# compass.net
KiCad netlist of a schematic drawn in EAGLE
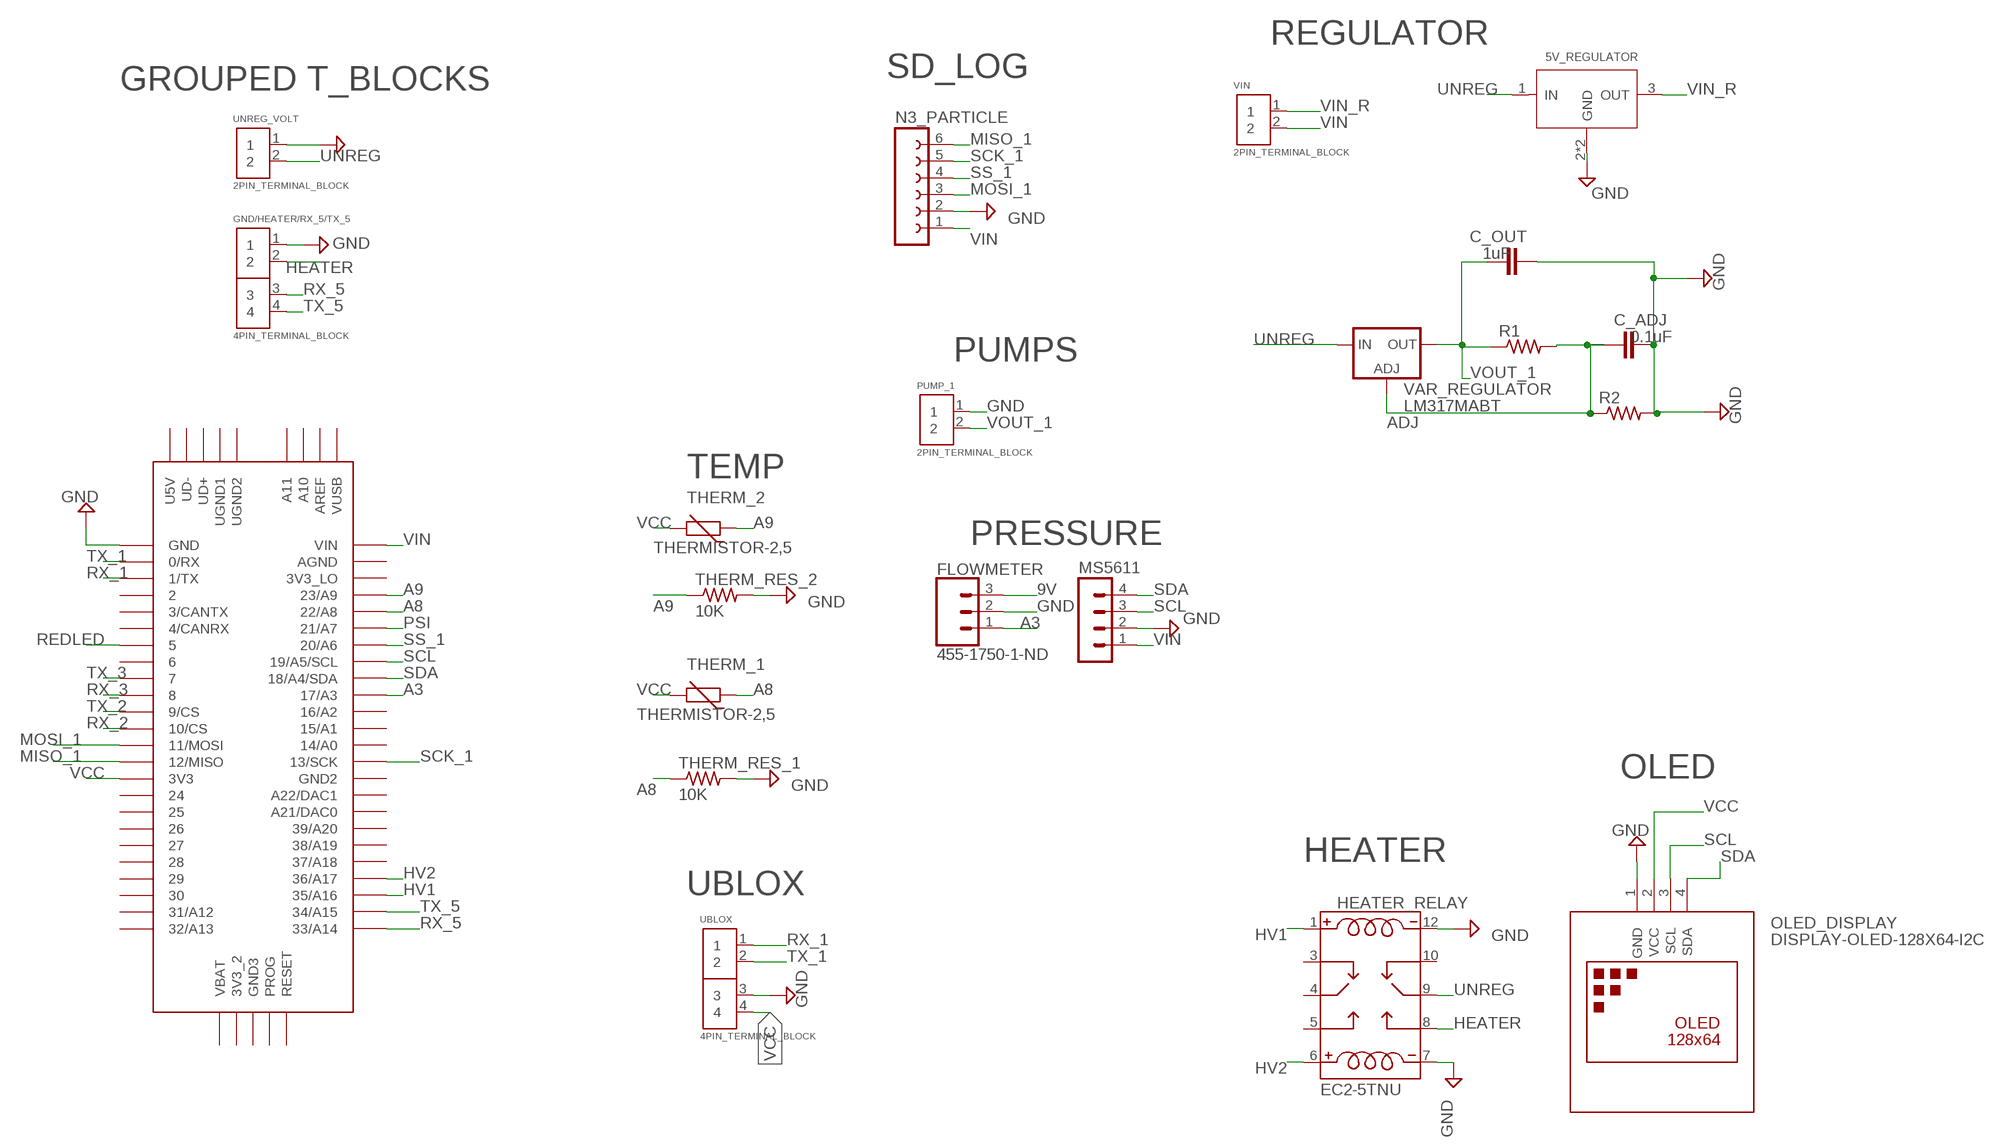
[diagram p0: schematic, sheet 1]

(export (version "E")
  (design (tool "Eeschema 10.0.6"))
  (components
    (comp (ref "5V_REGULATOR")
      (value "PMIC-L7805CV-DG(TO-220)")
      (footprint "eagle-import:TO-220")
      (fields
        (field (name "DIGI-KEY_PART_NUMBER") "497-12404-ND")
        (field (name "MF") "STMicroelectronics")
        (field (name "MP") "L7805CV-DG")
      )
      (libsource (lib "eagle-import") (part "PMIC-L7805CV-DG(TO-220)"))
    )
    (comp (ref "C_ADJ")
      (value "0.1uF")
      (footprint "eagle-import:C2.5-3")
      (libsource (lib "eagle-import") (part "C2,5-3"))
    )
    (comp (ref "C_OUT")
      (value "1uF")
      (footprint "eagle-import:C2.5-3")
      (libsource (lib "eagle-import") (part "C2,5-3"))
    )
    (comp (ref "FLOWMETER")
      (value "455-1750-1-ND")
      (footprint "eagle-import:1X03")
      (libsource (lib "eagle-import") (part "CONN_03"))
    )
    (comp (ref "GND/HEATER/RX_5/TX_5")
      (value "4PIN_TERMINAL_BLOCK")
      (footprint "eagle-import:4PIN_TERMINAL_BLOCK")
      (libsource (lib "eagle-import") (part "4PIN_TERMINAL_BLOCK"))
    )
    (comp (ref "HEATER_RELAY")
      (value "EC2-5TNU")
      (footprint "eagle-import:RELAY_EC2-5TNU")
      (fields (field (name "MF") "KEMET"))
      (libsource (lib "eagle-import") (part "EC2-5TNU"))
    )
    (comp (ref "MS5611")
      (value "MA04-1")
      (footprint "eagle-import:MA04-1")
      (libsource (lib "eagle-import") (part "MA04-1"))
    )
    (comp (ref "N3_PARTICLE")
      (value "FE06-1")
      (footprint "eagle-import:FE06")
      (libsource (lib "eagle-import") (part "FE06-1"))
    )
    (comp (ref "OLED_DISPLAY")
      (value "DISPLAY-OLED-128X64-I2C")
      (footprint "eagle-import:DISPLAY-OLED-128X64-I2C")
      (libsource (lib "eagle-import") (part "DISPLAY-OLED-128X64-I2C"))
    )
    (comp (ref "PUMP_1")
      (value "2PIN_TERMINAL_BLOCK")
      (footprint "eagle-import:2PIN_TERMINAL_BLOCK")
      (fields
        (field (name "COMMENT") "282834-2")
        (field (name "DIGI-KEY_PART_NUMBER") "A98333-ND")
        (field (name "MF") "TE Connectivity")
      )
      (libsource (lib "eagle-import") (part "2PIN_TERMINAL_BLOCK"))
    )
    (comp (ref "R1")
      (value "R-US_0204/7")
      (footprint "eagle-import:0204_7")
      (libsource (lib "eagle-import") (part "R-US_0204/7"))
    )
    (comp (ref "R2")
      (value "R-US_0204/7")
      (footprint "eagle-import:0204_7")
      (libsource (lib "eagle-import") (part "R-US_0204/7"))
    )
    (comp (ref "THERM_1")
      (value "THERMISTOR-2,5")
      (footprint "eagle-import:RS-2,5")
      (libsource (lib "eagle-import") (part "THERMISTOR-2,5"))
    )
    (comp (ref "THERM_2")
      (value "THERMISTOR-2,5")
      (footprint "eagle-import:RS-2,5")
      (libsource (lib "eagle-import") (part "THERMISTOR-2,5"))
    )
    (comp (ref "THERM_RES_1")
      (value "10K")
      (footprint "eagle-import:0204_7")
      (libsource (lib "eagle-import") (part "R-US_0204/7"))
    )
    (comp (ref "THERM_RES_2")
      (value "10K")
      (footprint "eagle-import:0204_7")
      (libsource (lib "eagle-import") (part "R-US_0204/7"))
    )
    (comp (ref "U$1")
      (value "TEENSY_3.5/3.6")
      (footprint "eagle-import:TEENSY_3.5_3.6")
      (libsource (lib "eagle-import") (part "TEENSY_3.5/3.6"))
    )
    (comp (ref "UBLOX")
      (value "4PIN_TERMINAL_BLOCK")
      (footprint "eagle-import:4PIN_TERMINAL_BLOCK")
      (libsource (lib "eagle-import") (part "4PIN_TERMINAL_BLOCK"))
    )
    (comp (ref "UNREG_VOLT")
      (value "2PIN_TERMINAL_BLOCK")
      (footprint "eagle-import:2PIN_TERMINAL_BLOCK")
      (fields
        (field (name "COMMENT") "282834-2")
        (field (name "DIGI-KEY_PART_NUMBER") "A98333-ND")
        (field (name "MF") "TE Connectivity")
      )
      (libsource (lib "eagle-import") (part "2PIN_TERMINAL_BLOCK"))
    )
    (comp (ref "VAR_REGULATOR")
      (value "LM317MABT")
      (footprint "eagle-import:TO220L1")
      (libsource (lib "eagle-import") (part "LM317?MABT"))
    )
    (comp (ref "VIN")
      (value "2PIN_TERMINAL_BLOCK")
      (footprint "eagle-import:2PIN_TERMINAL_BLOCK")
      (fields
        (field (name "COMMENT") "282834-2")
        (field (name "DIGI-KEY_PART_NUMBER") "A98333-ND")
        (field (name "MF") "TE Connectivity")
      )
      (libsource (lib "eagle-import") (part "2PIN_TERMINAL_BLOCK"))
    )
  )
  (nets
    (net (code "1") (name "/9V") (class "Default")
      (node (ref "FLOWMETER") (pin "3") (pinfunction "3_3") (pintype "passive"))
    )
    (net (code "2") (name "/A3") (class "Default")
      (node (ref "FLOWMETER") (pin "1") (pinfunction "1_1") (pintype "passive"))
      (node (ref "U$1") (pin "17/A3") (pinfunction "17/A3_17/A3") (pintype "bidirectional"))
    )
    (net (code "3") (name "/A8") (class "Default")
      (node (ref "THERM_1") (pin "1") (pinfunction "1_1") (pintype "passive"))
      (node (ref "THERM_RES_1") (pin "1") (pinfunction "1_1") (pintype "passive"))
      (node (ref "U$1") (pin "22/A8") (pinfunction "22/A8_22/A8") (pintype "bidirectional"))
    )
    (net (code "4") (name "/A9") (class "Default")
      (node (ref "THERM_2") (pin "1") (pinfunction "1_1") (pintype "passive"))
      (node (ref "THERM_RES_2") (pin "1") (pinfunction "1_1") (pintype "passive"))
      (node (ref "U$1") (pin "23/A9") (pinfunction "23/A9_23/A9") (pintype "bidirectional"))
    )
    (net (code "5") (name "/ADJ") (class "Default")
      (node (ref "C_ADJ") (pin "2") (pinfunction "2_2") (pintype "passive"))
      (node (ref "R1") (pin "2") (pinfunction "2_2") (pintype "passive"))
      (node (ref "R2") (pin "1") (pinfunction "1_1") (pintype "passive"))
      (node (ref "VAR_REGULATOR") (pin "1") (pinfunction "ADJ_1") (pintype "input"))
    )
    (net (code "6") (name "/HEATER") (class "Default")
      (node (ref "GND/HEATER/RX_5/TX_5") (pin "2") (pinfunction "2_2") (pintype "passive"))
      (node (ref "HEATER_RELAY") (pin "8") (pinfunction "NO_8") (pintype "passive"))
    )
    (net (code "7") (name "/HV1") (class "Default")
      (node (ref "HEATER_RELAY") (pin "1") (pinfunction "C1_1") (pintype "passive"))
      (node (ref "U$1") (pin "35/A16") (pinfunction "35/A16_35/A16") (pintype "bidirectional"))
    )
    (net (code "8") (name "/HV2") (class "Default")
      (node (ref "HEATER_RELAY") (pin "6") (pinfunction "C3_6") (pintype "passive"))
      (node (ref "U$1") (pin "36/A17") (pinfunction "36/A17_36/A17") (pintype "bidirectional"))
    )
    (net (code "9") (name "/MISO_1") (class "Default")
      (node (ref "N3_PARTICLE") (pin "6") (pinfunction "6_6") (pintype "passive"))
      (node (ref "U$1") (pin "12/MISO") (pinfunction "12/MISO_12/MISO") (pintype "bidirectional"))
    )
    (net (code "10") (name "/MOSI_1") (class "Default")
      (node (ref "N3_PARTICLE") (pin "3") (pinfunction "3_3") (pintype "passive"))
      (node (ref "U$1") (pin "11/MOSI") (pinfunction "11/MOSI_11/MOSI") (pintype "bidirectional"))
    )
    (net (code "11") (name "/PSI") (class "Default")
      (node (ref "U$1") (pin "21/A7") (pinfunction "21/A7_21/A7") (pintype "bidirectional"))
    )
    (net (code "12") (name "/REDLED") (class "Default")
      (node (ref "U$1") (pin "5") (pinfunction "5_5") (pintype "bidirectional"))
    )
    (net (code "13") (name "/RX_1") (class "Default")
      (node (ref "U$1") (pin "1/TX") (pinfunction "1/TX_1/TX") (pintype "bidirectional"))
      (node (ref "UBLOX") (pin "1") (pinfunction "1_1") (pintype "passive"))
    )
    (net (code "14") (name "/RX_2") (class "Default")
      (node (ref "U$1") (pin "10/CS") (pinfunction "10/CS_10/CS") (pintype "bidirectional"))
    )
    (net (code "15") (name "/RX_3") (class "Default")
      (node (ref "U$1") (pin "8") (pinfunction "8_8") (pintype "bidirectional"))
    )
    (net (code "16") (name "/RX_5") (class "Default")
      (node (ref "GND/HEATER/RX_5/TX_5") (pin "3") (pinfunction "3_3") (pintype "passive"))
      (node (ref "U$1") (pin "33/A14") (pinfunction "33/A14_33/A14") (pintype "bidirectional"))
    )
    (net (code "17") (name "/SCK_1") (class "Default")
      (node (ref "N3_PARTICLE") (pin "5") (pinfunction "5_5") (pintype "passive"))
      (node (ref "U$1") (pin "13/SCK") (pinfunction "13/SCK_13/SCK") (pintype "bidirectional"))
    )
    (net (code "18") (name "/SCL") (class "Default")
      (node (ref "MS5611") (pin "3") (pinfunction "3_3") (pintype "passive"))
      (node (ref "OLED_DISPLAY") (pin "3") (pinfunction "SCL_3") (pintype "bidirectional"))
      (node (ref "U$1") (pin "19/A5/SCL") (pinfunction "19/A5/SCL_19/A5/SCL") (pintype "bidirectional"))
    )
    (net (code "19") (name "/SDA") (class "Default")
      (node (ref "MS5611") (pin "4") (pinfunction "4_4") (pintype "passive"))
      (node (ref "OLED_DISPLAY") (pin "4") (pinfunction "SDA_4") (pintype "bidirectional"))
      (node (ref "U$1") (pin "18/A4/SDA") (pinfunction "18/A4/SDA_18/A4/SDA") (pintype "bidirectional"))
    )
    (net (code "20") (name "/SS_1") (class "Default")
      (node (ref "N3_PARTICLE") (pin "4") (pinfunction "4_4") (pintype "passive"))
      (node (ref "U$1") (pin "20/A6") (pinfunction "20/A6_20/A6") (pintype "bidirectional"))
    )
    (net (code "21") (name "/TX_1") (class "Default")
      (node (ref "U$1") (pin "0/RX") (pinfunction "0/RX_0/RX") (pintype "bidirectional"))
      (node (ref "UBLOX") (pin "2") (pinfunction "2_2") (pintype "passive"))
    )
    (net (code "22") (name "/TX_2") (class "Default")
      (node (ref "U$1") (pin "9/CS") (pinfunction "9/CS_9/CS") (pintype "bidirectional"))
    )
    (net (code "23") (name "/TX_3") (class "Default")
      (node (ref "U$1") (pin "7") (pinfunction "7_7") (pintype "bidirectional"))
    )
    (net (code "24") (name "/TX_5") (class "Default")
      (node (ref "GND/HEATER/RX_5/TX_5") (pin "4") (pinfunction "4_4") (pintype "passive"))
      (node (ref "U$1") (pin "34/A15") (pinfunction "34/A15_34/A15") (pintype "bidirectional"))
    )
    (net (code "25") (name "/UNREG") (class "Default")
      (node (ref "5V_REGULATOR") (pin "1") (pinfunction "IN_1") (pintype "bidirectional"))
      (node (ref "HEATER_RELAY") (pin "9") (pinfunction "M_9") (pintype "passive"))
      (node (ref "UNREG_VOLT") (pin "2") (pinfunction "2_2") (pintype "passive"))
      (node (ref "VAR_REGULATOR") (pin "3") (pinfunction "IN_3") (pintype "input"))
    )
    (net (code "26") (name "/VIN") (class "Default")
      (node (ref "MS5611") (pin "1") (pinfunction "1_1") (pintype "passive"))
      (node (ref "N3_PARTICLE") (pin "1") (pinfunction "1_1") (pintype "passive"))
      (node (ref "U$1") (pin "VIN") (pinfunction "VIN_VIN") (pintype "bidirectional"))
      (node (ref "VIN") (pin "2") (pinfunction "2_2") (pintype "passive"))
    )
    (net (code "27") (name "/VIN_R") (class "Default")
      (node (ref "5V_REGULATOR") (pin "3") (pinfunction "OUT_3") (pintype "bidirectional"))
      (node (ref "VIN") (pin "1") (pinfunction "1_1") (pintype "passive"))
    )
    (net (code "28") (name "/VOUT_1") (class "Default")
      (node (ref "C_OUT") (pin "1") (pinfunction "1_1") (pintype "passive"))
      (node (ref "PUMP_1") (pin "2") (pinfunction "2_2") (pintype "passive"))
      (node (ref "R1") (pin "1") (pinfunction "1_1") (pintype "passive"))
      (node (ref "VAR_REGULATOR") (pin "2") (pinfunction "OUT_2") (pintype "passive"))
    )
    (net (code "29") (name "GND") (class "Default")
      (node (ref "5V_REGULATOR") (pin "2") (pinfunction "GND_2") (pintype "bidirectional"))
      (node (ref "5V_REGULATOR") (pin "HEAT") (pinfunction "GND_HEAT") (pintype "bidirectional"))
      (node (ref "C_ADJ") (pin "1") (pinfunction "1_1") (pintype "passive"))
      (node (ref "C_OUT") (pin "2") (pinfunction "2_2") (pintype "passive"))
      (node (ref "FLOWMETER") (pin "2") (pinfunction "2_2") (pintype "passive"))
      (node (ref "GND/HEATER/RX_5/TX_5") (pin "1") (pinfunction "1_1") (pintype "passive"))
      (node (ref "HEATER_RELAY") (pin "12") (pinfunction "C2_12") (pintype "passive"))
      (node (ref "HEATER_RELAY") (pin "7") (pinfunction "C4_7") (pintype "passive"))
      (node (ref "MS5611") (pin "2") (pinfunction "2_2") (pintype "passive"))
      (node (ref "N3_PARTICLE") (pin "2") (pinfunction "2_2") (pintype "passive"))
      (node (ref "OLED_DISPLAY") (pin "1") (pinfunction "GND_1") (pintype "power_in"))
      (node (ref "PUMP_1") (pin "1") (pinfunction "1_1") (pintype "passive"))
      (node (ref "R2") (pin "2") (pinfunction "2_2") (pintype "passive"))
      (node (ref "THERM_RES_1") (pin "2") (pinfunction "2_2") (pintype "passive"))
      (node (ref "THERM_RES_2") (pin "2") (pinfunction "2_2") (pintype "passive"))
      (node (ref "U$1") (pin "GND") (pinfunction "GND_GND") (pintype "bidirectional"))
      (node (ref "UBLOX") (pin "3") (pinfunction "3_3") (pintype "passive"))
      (node (ref "UNREG_VOLT") (pin "1") (pinfunction "1_1") (pintype "passive"))
    )
    (net (code "30") (name "VCC") (class "Default")
      (node (ref "OLED_DISPLAY") (pin "2") (pinfunction "VCC_2") (pintype "power_in"))
      (node (ref "THERM_1") (pin "2") (pinfunction "2_2") (pintype "passive"))
      (node (ref "THERM_2") (pin "2") (pinfunction "2_2") (pintype "passive"))
      (node (ref "U$1") (pin "3V3") (pinfunction "3V3_3V3") (pintype "bidirectional"))
      (node (ref "UBLOX") (pin "4") (pinfunction "4_4") (pintype "passive"))
    )
    (net (code "31") (name "unconnected-(HEATER_RELAY-M1-Pad4)") (class "Default")
      (node (ref "HEATER_RELAY") (pin "4") (pinfunction "M1_4") (pintype "passive"))
    )
    (net (code "32") (name "unconnected-(HEATER_RELAY-NC-Pad10)") (class "Default")
      (node (ref "HEATER_RELAY") (pin "10") (pinfunction "NC_10") (pintype "passive"))
    )
    (net (code "33") (name "unconnected-(HEATER_RELAY-NC1-Pad3)") (class "Default")
      (node (ref "HEATER_RELAY") (pin "3") (pinfunction "NC1_3") (pintype "passive"))
    )
    (net (code "34") (name "unconnected-(HEATER_RELAY-NO1-Pad5)") (class "Default")
      (node (ref "HEATER_RELAY") (pin "5") (pinfunction "NO1_5") (pintype "passive"))
    )
    (net (code "35") (name "unconnected-(U$1-A21{slash}DAC0-Pad21{slash}DAC0)") (class "Default")
      (node (ref "U$1") (pin "21/DAC0") (pinfunction "A21/DAC0_21/DAC0") (pintype "bidirectional"))
    )
    (net (code "36") (name "unconnected-(U$1-Pad2)") (class "Default")
      (node (ref "U$1") (pin "2") (pinfunction "2_2") (pintype "bidirectional"))
    )
    (net (code "37") (name "unconnected-(U$1-Pad3V3_2)") (class "Default")
      (node (ref "U$1") (pin "3V3_2") (pinfunction "3V3_2_3V3_2") (pintype "bidirectional"))
    )
    (net (code "38") (name "unconnected-(U$1-Pad3V3_LO)") (class "Default")
      (node (ref "U$1") (pin "3V3_LO") (pinfunction "3V3_LO_3V3_LO") (pintype "bidirectional"))
    )
    (net (code "39") (name "unconnected-(U$1-Pad3{slash}CANTX)") (class "Default")
      (node (ref "U$1") (pin "3/CANTX") (pinfunction "3/CANTX_3/CANTX") (pintype "bidirectional"))
    )
    (net (code "40") (name "unconnected-(U$1-Pad4{slash}CANRX)") (class "Default")
      (node (ref "U$1") (pin "4/CANRX") (pinfunction "4/CANRX_4/CANRX") (pintype "bidirectional"))
    )
    (net (code "41") (name "unconnected-(U$1-Pad6)") (class "Default")
      (node (ref "U$1") (pin "6") (pinfunction "6_6") (pintype "bidirectional"))
    )
    (net (code "42") (name "unconnected-(U$1-Pad14{slash}A0)") (class "Default")
      (node (ref "U$1") (pin "14/A0") (pinfunction "14/A0_14/A0") (pintype "bidirectional"))
    )
    (net (code "43") (name "unconnected-(U$1-Pad15{slash}A1)") (class "Default")
      (node (ref "U$1") (pin "15/A1") (pinfunction "15/A1_15/A1") (pintype "bidirectional"))
    )
    (net (code "44") (name "unconnected-(U$1-Pad16{slash}A2)") (class "Default")
      (node (ref "U$1") (pin "16/A2") (pinfunction "16/A2_16/A2") (pintype "bidirectional"))
    )
    (net (code "45") (name "unconnected-(U$1-Pad24)") (class "Default")
      (node (ref "U$1") (pin "24") (pinfunction "24_24") (pintype "bidirectional"))
    )
    (net (code "46") (name "unconnected-(U$1-Pad25)") (class "Default")
      (node (ref "U$1") (pin "25") (pinfunction "25_25") (pintype "bidirectional"))
    )
    (net (code "47") (name "unconnected-(U$1-Pad26)") (class "Default")
      (node (ref "U$1") (pin "26") (pinfunction "26_26") (pintype "bidirectional"))
    )
    (net (code "48") (name "unconnected-(U$1-Pad27)") (class "Default")
      (node (ref "U$1") (pin "27") (pinfunction "27_27") (pintype "bidirectional"))
    )
    (net (code "49") (name "unconnected-(U$1-Pad28)") (class "Default")
      (node (ref "U$1") (pin "28") (pinfunction "28_28") (pintype "bidirectional"))
    )
    (net (code "50") (name "unconnected-(U$1-Pad29)") (class "Default")
      (node (ref "U$1") (pin "29") (pinfunction "29_29") (pintype "bidirectional"))
    )
    (net (code "51") (name "unconnected-(U$1-Pad30)") (class "Default")
      (node (ref "U$1") (pin "30") (pinfunction "30_30") (pintype "bidirectional"))
    )
    (net (code "52") (name "unconnected-(U$1-Pad31{slash}A12)") (class "Default")
      (node (ref "U$1") (pin "31/A12") (pinfunction "31/A12_31/A12") (pintype "bidirectional"))
    )
    (net (code "53") (name "unconnected-(U$1-Pad32{slash}A13)") (class "Default")
      (node (ref "U$1") (pin "32/A13") (pinfunction "32/A13_32/A13") (pintype "bidirectional"))
    )
    (net (code "54") (name "unconnected-(U$1-Pad37{slash}A18)") (class "Default")
      (node (ref "U$1") (pin "37/A18") (pinfunction "37/A18_37/A18") (pintype "bidirectional"))
    )
    (net (code "55") (name "unconnected-(U$1-Pad38{slash}A19)") (class "Default")
      (node (ref "U$1") (pin "38/A19") (pinfunction "38/A19_38/A19") (pintype "bidirectional"))
    )
    (net (code "56") (name "unconnected-(U$1-Pad39{slash}A20)") (class "Default")
      (node (ref "U$1") (pin "39/A20") (pinfunction "39/A20_39/A20") (pintype "bidirectional"))
    )
    (net (code "57") (name "unconnected-(U$1-PadA10)") (class "Default")
      (node (ref "U$1") (pin "A10") (pinfunction "A10_A10") (pintype "bidirectional"))
    )
    (net (code "58") (name "unconnected-(U$1-PadA11)") (class "Default")
      (node (ref "U$1") (pin "A11") (pinfunction "A11_A11") (pintype "bidirectional"))
    )
    (net (code "59") (name "unconnected-(U$1-PadA22{slash}DAC1)") (class "Default")
      (node (ref "U$1") (pin "A22/DAC1") (pinfunction "A22/DAC1_A22/DAC1") (pintype "bidirectional"))
    )
    (net (code "60") (name "unconnected-(U$1-PadAGND)") (class "Default")
      (node (ref "U$1") (pin "AGND") (pinfunction "AGND_AGND") (pintype "bidirectional"))
    )
    (net (code "61") (name "unconnected-(U$1-PadAREF)") (class "Default")
      (node (ref "U$1") (pin "AREF") (pinfunction "AREF_AREF") (pintype "bidirectional"))
    )
    (net (code "62") (name "unconnected-(U$1-PadGND2)") (class "Default")
      (node (ref "U$1") (pin "GND2") (pinfunction "GND2_GND2") (pintype "bidirectional"))
    )
    (net (code "63") (name "unconnected-(U$1-PadGND3)") (class "Default")
      (node (ref "U$1") (pin "GND3") (pinfunction "GND3_GND3") (pintype "bidirectional"))
    )
    (net (code "64") (name "unconnected-(U$1-PadPROG)") (class "Default")
      (node (ref "U$1") (pin "PROG") (pinfunction "PROG_PROG") (pintype "bidirectional"))
    )
    (net (code "65") (name "unconnected-(U$1-PadRESET)") (class "Default")
      (node (ref "U$1") (pin "RESET") (pinfunction "RESET_RESET") (pintype "bidirectional"))
    )
    (net (code "66") (name "unconnected-(U$1-PadU5V)") (class "Default")
      (node (ref "U$1") (pin "U5V") (pinfunction "U5V_U5V") (pintype "bidirectional"))
    )
    (net (code "67") (name "unconnected-(U$1-PadUD+)") (class "Default")
      (node (ref "U$1") (pin "UD+") (pinfunction "UD+_UD+") (pintype "bidirectional"))
    )
    (net (code "68") (name "unconnected-(U$1-PadUD-)") (class "Default")
      (node (ref "U$1") (pin "UD-") (pinfunction "UD-_UD-") (pintype "bidirectional"))
    )
    (net (code "69") (name "unconnected-(U$1-PadUGND1)") (class "Default")
      (node (ref "U$1") (pin "UGND1") (pinfunction "UGND1_UGND1") (pintype "bidirectional"))
    )
    (net (code "70") (name "unconnected-(U$1-PadUGND2)") (class "Default")
      (node (ref "U$1") (pin "UGND2") (pinfunction "UGND2_UGND2") (pintype "bidirectional"))
    )
    (net (code "71") (name "unconnected-(U$1-PadVBAT)") (class "Default")
      (node (ref "U$1") (pin "VBAT") (pinfunction "VBAT_VBAT") (pintype "bidirectional"))
    )
    (net (code "72") (name "unconnected-(U$1-PadVUSB)") (class "Default")
      (node (ref "U$1") (pin "VUSB") (pinfunction "VUSB_VUSB") (pintype "bidirectional"))
    )
  )
)
